# 220V_1500Watt_Masttech.net
KiCad netlist of a schematic drawn in EasyEDA
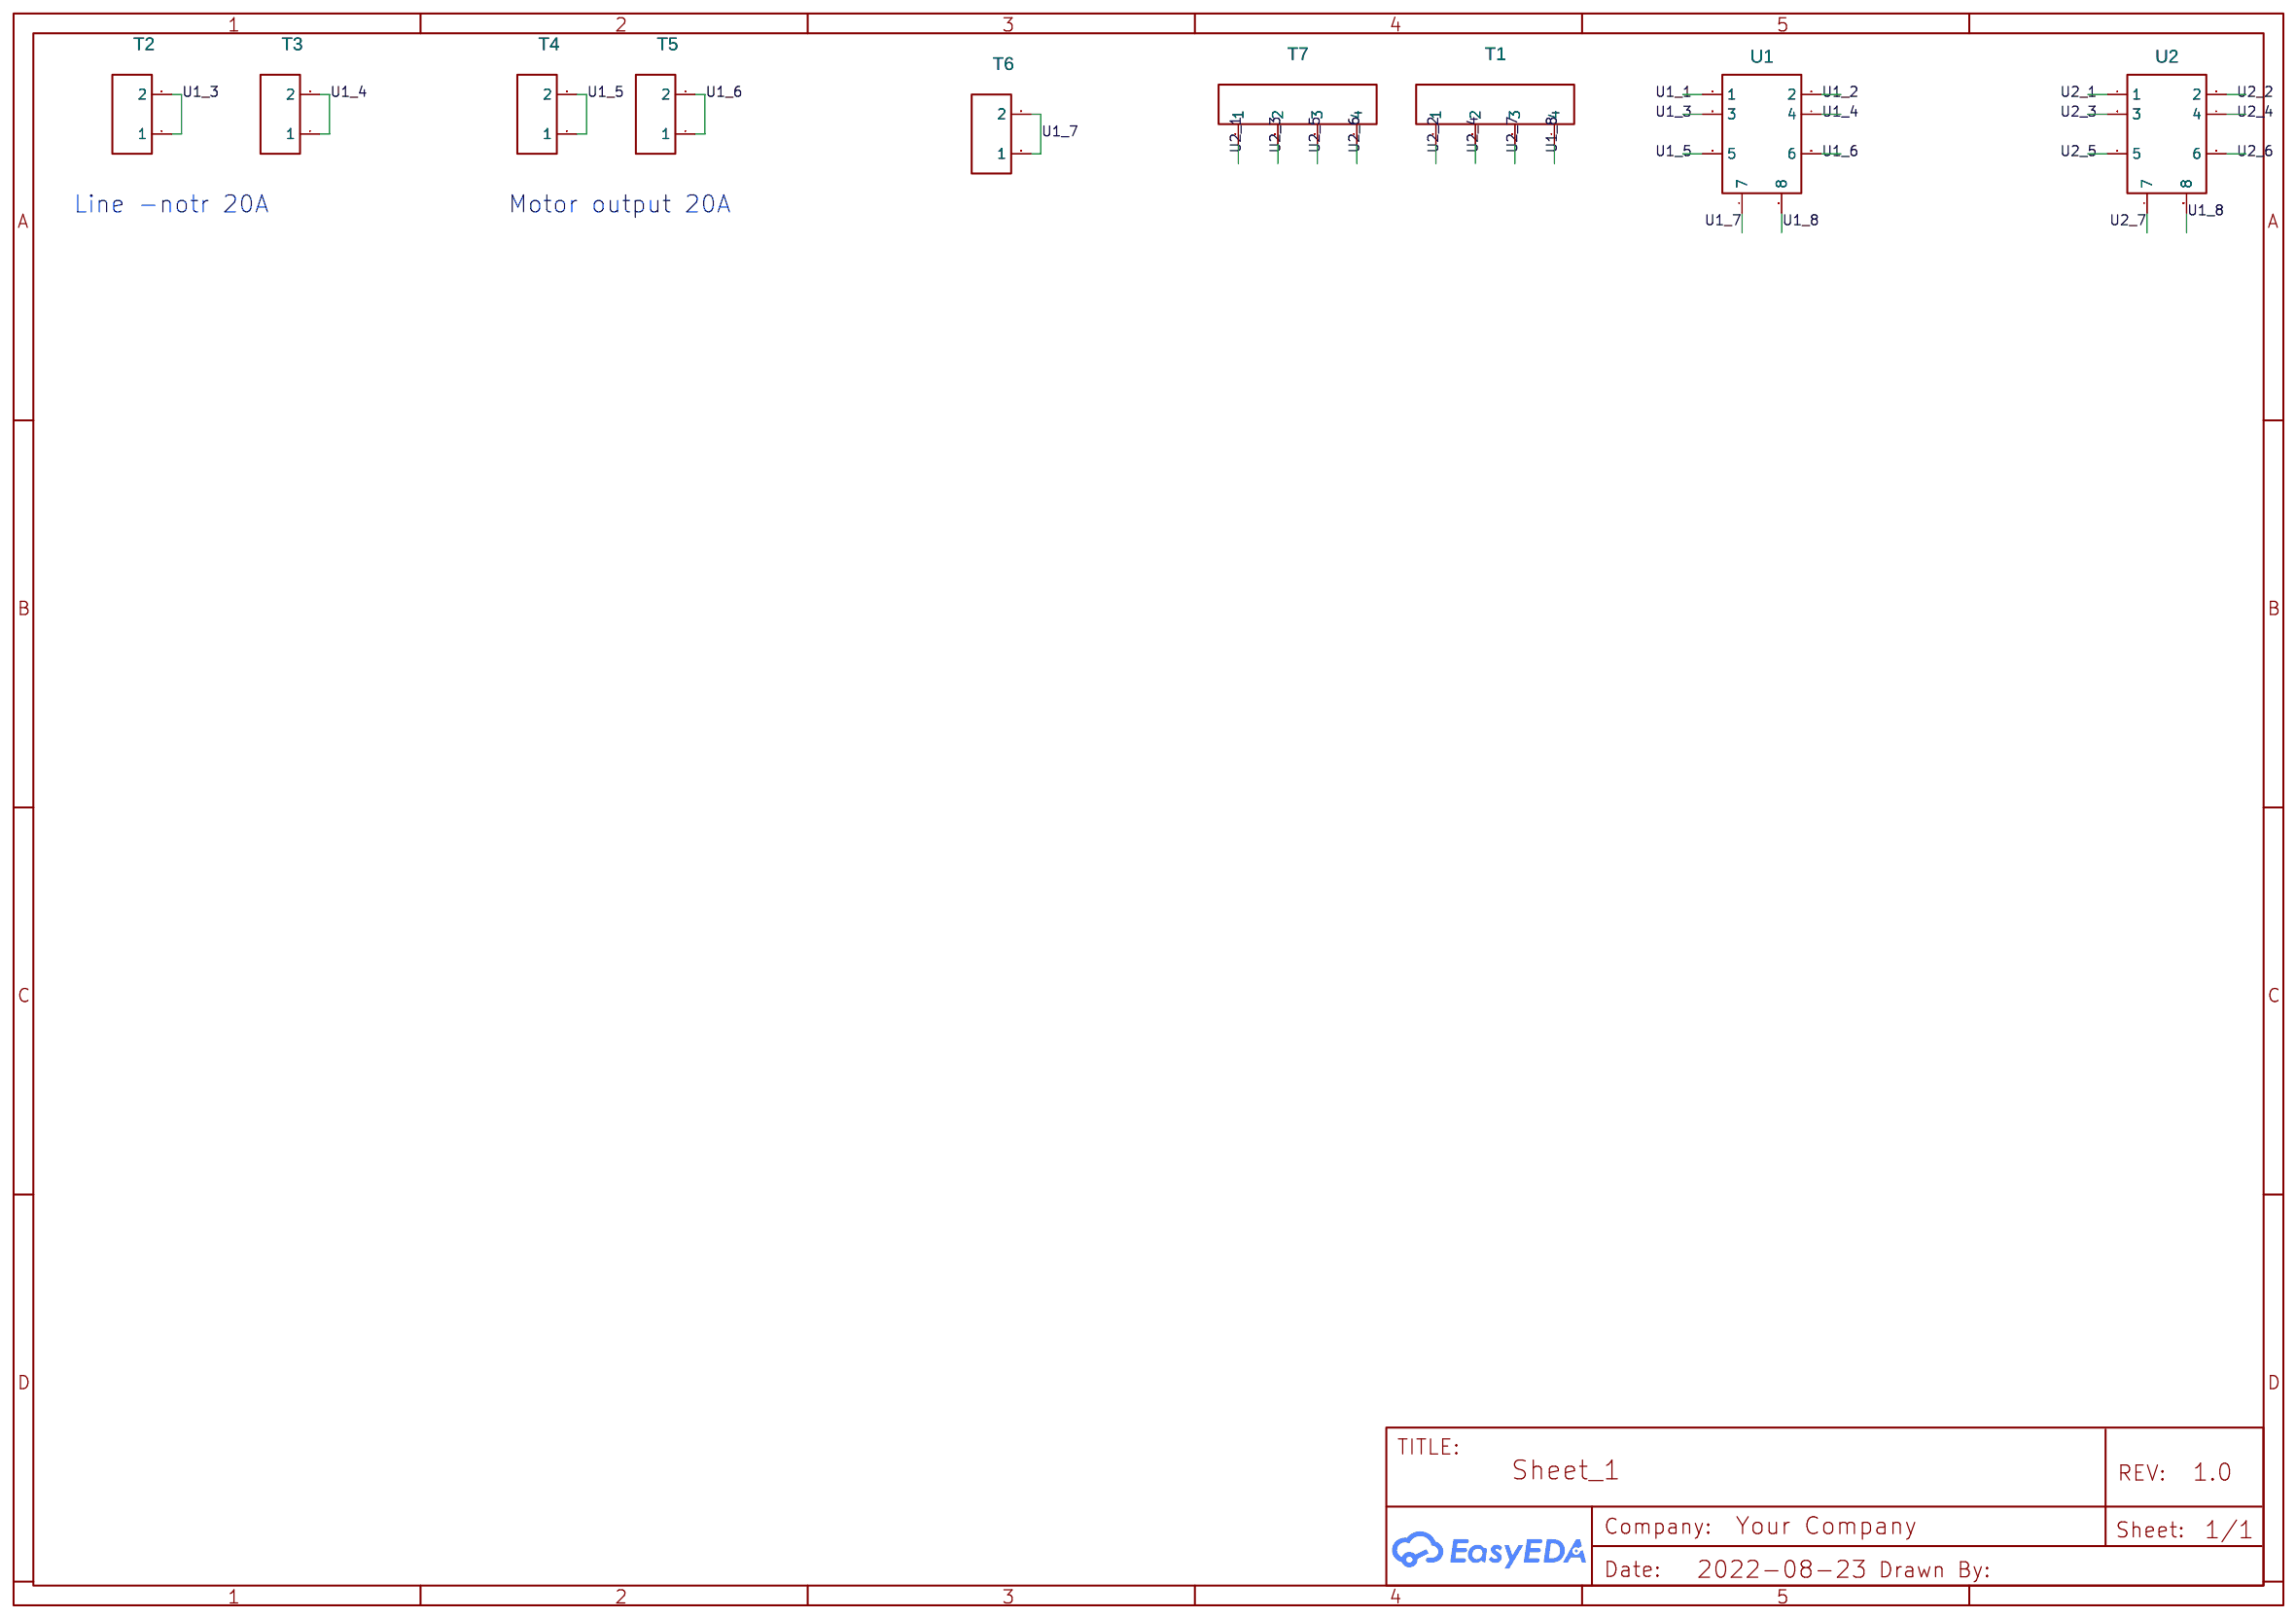
[diagram p0: schematic sheet]

(export (version "E")
  (design (tool "Eeschema 10.0.6"))
  (components
    (comp (ref "T1") (value "1x4 6A Terminal") (libsource (lib "") (part "1x4 6A Terminal")))
    (comp (ref "T2") (value "1x2 30A Molex Terminal") (libsource (lib "") (part "1x2 30A Molex Terminal")))
    (comp (ref "T3") (value "1x2 30A Molex Terminal") (libsource (lib "") (part "1x2 30A Molex Terminal")))
    (comp (ref "T4") (value "1x2 30A Molex Terminal") (libsource (lib "") (part "1x2 30A Molex Terminal")))
    (comp (ref "T5") (value "1x2 30A Molex Terminal") (libsource (lib "") (part "1x2 30A Molex Terminal")))
    (comp (ref "T6") (value "1x2 30A Molex Terminal") (libsource (lib "") (part "1x2 30A Molex Terminal")))
    (comp (ref "T7") (value "1x4 6A Terminal") (libsource (lib "") (part "1x4 6A Terminal")))
    (comp (ref "U1") (value "relay_56.32") (libsource (lib "") (part "relay_56.32")))
    (comp (ref "U2") (value "relay_56.32") (libsource (lib "") (part "relay_56.32")))
  )
  (nets
    (net (code "1") (name "/U1_1") (class "Default")
      (node (ref "U1") (pin "1") (pinfunction "1_1") (pintype "unspecified"))
    )
    (net (code "2") (name "/U1_2") (class "Default")
      (node (ref "U1") (pin "2") (pinfunction "2_2") (pintype "unspecified"))
    )
    (net (code "3") (name "/U1_3") (class "Default")
      (node (ref "T2") (pin "1") (pinfunction "1_1") (pintype "unspecified"))
      (node (ref "T2") (pin "2") (pinfunction "2_2") (pintype "unspecified"))
      (node (ref "U1") (pin "3") (pinfunction "3_3") (pintype "unspecified"))
    )
    (net (code "4") (name "/U1_4") (class "Default")
      (node (ref "T3") (pin "1") (pinfunction "1_1") (pintype "unspecified"))
      (node (ref "T3") (pin "2") (pinfunction "2_2") (pintype "unspecified"))
      (node (ref "U1") (pin "4") (pinfunction "4_4") (pintype "unspecified"))
    )
    (net (code "5") (name "/U1_5") (class "Default")
      (node (ref "T4") (pin "1") (pinfunction "1_1") (pintype "unspecified"))
      (node (ref "T4") (pin "2") (pinfunction "2_2") (pintype "unspecified"))
      (node (ref "U1") (pin "5") (pinfunction "5_5") (pintype "unspecified"))
    )
    (net (code "6") (name "/U1_6") (class "Default")
      (node (ref "T5") (pin "1") (pinfunction "1_1") (pintype "unspecified"))
      (node (ref "T5") (pin "2") (pinfunction "2_2") (pintype "unspecified"))
      (node (ref "U1") (pin "6") (pinfunction "6_6") (pintype "unspecified"))
    )
    (net (code "7") (name "/U1_7") (class "Default")
      (node (ref "T6") (pin "1") (pinfunction "1_1") (pintype "unspecified"))
      (node (ref "T6") (pin "2") (pinfunction "2_2") (pintype "unspecified"))
      (node (ref "U1") (pin "7") (pinfunction "7_7") (pintype "unspecified"))
    )
    (net (code "8") (name "/U1_8") (class "Default")
      (node (ref "T1") (pin "4") (pinfunction "4_4") (pintype "unspecified"))
      (node (ref "U1") (pin "8") (pinfunction "8_8") (pintype "unspecified"))
      (node (ref "U2") (pin "8") (pinfunction "8_8") (pintype "unspecified"))
    )
    (net (code "9") (name "/U2_1") (class "Default")
      (node (ref "T7") (pin "1") (pinfunction "1_1") (pintype "unspecified"))
      (node (ref "U2") (pin "1") (pinfunction "1_1") (pintype "unspecified"))
    )
    (net (code "10") (name "/U2_2") (class "Default")
      (node (ref "T1") (pin "1") (pinfunction "1_1") (pintype "unspecified"))
      (node (ref "U2") (pin "2") (pinfunction "2_2") (pintype "unspecified"))
    )
    (net (code "11") (name "/U2_3") (class "Default")
      (node (ref "T7") (pin "2") (pinfunction "2_2") (pintype "unspecified"))
      (node (ref "U2") (pin "3") (pinfunction "3_3") (pintype "unspecified"))
    )
    (net (code "12") (name "/U2_4") (class "Default")
      (node (ref "T1") (pin "2") (pinfunction "2_2") (pintype "unspecified"))
      (node (ref "U2") (pin "4") (pinfunction "4_4") (pintype "unspecified"))
    )
    (net (code "13") (name "/U2_5") (class "Default")
      (node (ref "T7") (pin "3") (pinfunction "3_3") (pintype "unspecified"))
      (node (ref "U2") (pin "5") (pinfunction "5_5") (pintype "unspecified"))
    )
    (net (code "14") (name "/U2_6") (class "Default")
      (node (ref "T7") (pin "4") (pinfunction "4_4") (pintype "unspecified"))
      (node (ref "U2") (pin "6") (pinfunction "6_6") (pintype "unspecified"))
    )
    (net (code "15") (name "/U2_7") (class "Default")
      (node (ref "T1") (pin "3") (pinfunction "3_3") (pintype "unspecified"))
      (node (ref "U2") (pin "7") (pinfunction "7_7") (pintype "unspecified"))
    )
  )
)
